# Port.net
KiCad netlist of a schematic drawn in Altium Designer
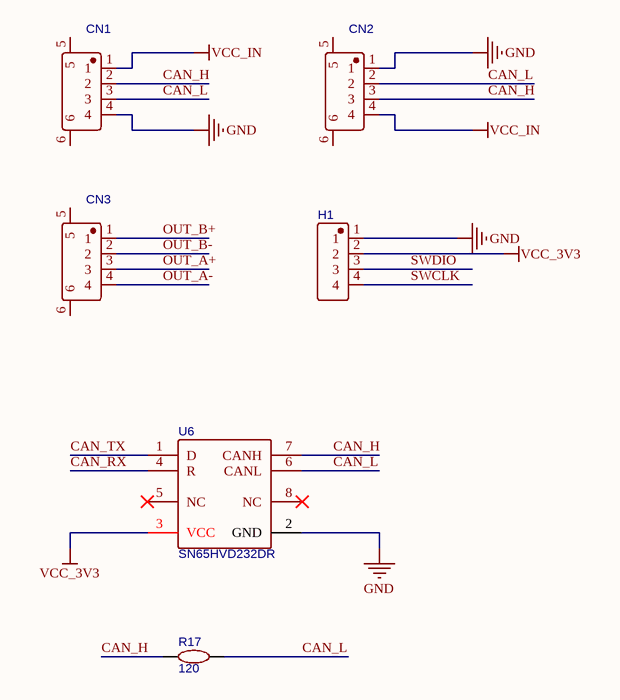
[diagram p0: Port.SchDoc]

(export (version "E")
  (design (tool "Eeschema 10.0.6"))
  (components
    (comp (ref "CN1")
      (value "~")
      (footprint "CONN-SMD_4P-P2.50-WAFER-254W-4P")
      (fields
        (field (name "BOM_SUPPLIER PART") "C2856745")
        (field (name "BOM_MANUFACTURER PART") "WAFER-254W-4P")
        (field (name "CONTRIBUTOR") "LCSC")
      )
      (libsource (lib "4P 2.54 WTB") (part "WAFER-254W-4P"))
    )
    (comp (ref "CN2")
      (value "~")
      (footprint "CONN-SMD_4P-P2.50-WAFER-254W-4P")
      (fields
        (field (name "BOM_SUPPLIER PART") "C2856745")
        (field (name "BOM_MANUFACTURER PART") "WAFER-254W-4P")
        (field (name "CONTRIBUTOR") "LCSC")
      )
      (libsource (lib "4P 2.54 WTB") (part "WAFER-254W-4P"))
    )
    (comp (ref "CN3")
      (value "~")
      (footprint "CONN-SMD_4P-P2.50-WAFER-254W-4P")
      (fields
        (field (name "BOM_SUPPLIER PART") "C2856745")
        (field (name "BOM_MANUFACTURER PART") "WAFER-254W-4P")
        (field (name "CONTRIBUTOR") "LCSC")
      )
      (libsource (lib "4P 2.54 WTB") (part "WAFER-254W-4P"))
    )
    (comp (ref "H1")
      (value "~")
      (footprint "HDR-TH_4P-P2.54-H-M-W10.4")
      (fields
        (field (name "BOM_SUPPLIER PART") "C91552")
        (field (name "BOM_MANUFACTURER PART") "2.54-1*4P反弯排针")
        (field (name "CONTRIBUTOR") "LCSC")
      )
      (libsource (lib "4P 2.54 bend") (part "2.54-1*4P反弯排针"))
    )
    (comp (ref "R17")
      (value "120")
      (footprint "R0603")
      (fields
        (field (name "BOM_MANUFACTURER PART") "0603WAF1200T5E")
        (field (name "BOM_SUPPLIER PART") "C22787")
      )
      (libsource (lib "120R") (part "120"))
    )
    (comp (ref "U6")
      (value "SN65HVD232DR")
      (footprint "SOIC-8_L5.0-W4.0-P1.27-LS6.0-BL")
      (fields (field (name "BOM_SUPPLIER PART") "C30530"))
      (libsource (lib "SN65HVD232DR") (part "SN65HVD232DR"))
    )
  )
  (nets
    (net (code "1") (name "/CAN_H") (class "Default")
      (node (ref "CN1") (pin "2") (pinfunction "2_2") (pintype "passive"))
      (node (ref "CN2") (pin "3") (pinfunction "3_3") (pintype "passive"))
      (node (ref "R17") (pin "1") (pinfunction "1_1") (pintype "passive"))
      (node (ref "U6") (pin "7") (pinfunction "CANH_7") (pintype "passive"))
    )
    (net (code "2") (name "/CAN_L") (class "Default")
      (node (ref "CN1") (pin "3") (pinfunction "3_3") (pintype "passive"))
      (node (ref "CN2") (pin "2") (pinfunction "2_2") (pintype "passive"))
      (node (ref "R17") (pin "2") (pinfunction "2_2") (pintype "passive"))
      (node (ref "U6") (pin "6") (pinfunction "CANL_6") (pintype "passive"))
    )
    (net (code "3") (name "/CAN_RX") (class "Default")
      (node (ref "U6") (pin "4") (pinfunction "R_4") (pintype "passive"))
    )
    (net (code "4") (name "/CAN_TX") (class "Default")
      (node (ref "U6") (pin "1") (pinfunction "D_1") (pintype "passive"))
    )
    (net (code "5") (name "/OUT_A+") (class "Default")
      (node (ref "CN3") (pin "3") (pinfunction "3_3") (pintype "passive"))
    )
    (net (code "6") (name "/OUT_A-") (class "Default")
      (node (ref "CN3") (pin "4") (pinfunction "4_4") (pintype "passive"))
    )
    (net (code "7") (name "/OUT_B+") (class "Default")
      (node (ref "CN3") (pin "1") (pinfunction "1_1") (pintype "passive"))
    )
    (net (code "8") (name "/OUT_B-") (class "Default")
      (node (ref "CN3") (pin "2") (pinfunction "2_2") (pintype "passive"))
    )
    (net (code "9") (name "/SWCLK") (class "Default")
      (node (ref "H1") (pin "4") (pinfunction "4_4") (pintype "passive"))
    )
    (net (code "10") (name "/SWDIO") (class "Default")
      (node (ref "H1") (pin "3") (pinfunction "3_3") (pintype "passive"))
    )
    (net (code "11") (name "GND") (class "Default")
      (node (ref "CN1") (pin "4") (pinfunction "4_4") (pintype "passive"))
      (node (ref "CN2") (pin "1") (pinfunction "1_1") (pintype "passive"))
      (node (ref "H1") (pin "1") (pinfunction "1_1") (pintype "passive"))
      (node (ref "U6") (pin "2") (pinfunction "GND_2") (pintype "passive"))
    )
    (net (code "12") (name "VCC_3V3") (class "Default")
      (node (ref "H1") (pin "2") (pinfunction "2_2") (pintype "passive"))
      (node (ref "U6") (pin "3") (pinfunction "VCC_3") (pintype "passive"))
    )
    (net (code "13") (name "VCC_IN") (class "Default")
      (node (ref "CN1") (pin "1") (pinfunction "1_1") (pintype "passive"))
      (node (ref "CN2") (pin "4") (pinfunction "4_4") (pintype "passive"))
    )
    (net (code "14") (name "unconnected-(CN1-Pad5)") (class "Default")
      (node (ref "CN1") (pin "5") (pinfunction "5_5") (pintype "passive"))
    )
    (net (code "15") (name "unconnected-(CN1-Pad6)") (class "Default")
      (node (ref "CN1") (pin "6") (pinfunction "6_6") (pintype "passive"))
    )
    (net (code "16") (name "unconnected-(CN2-Pad5)") (class "Default")
      (node (ref "CN2") (pin "5") (pinfunction "5_5") (pintype "passive"))
    )
    (net (code "17") (name "unconnected-(CN2-Pad6)") (class "Default")
      (node (ref "CN2") (pin "6") (pinfunction "6_6") (pintype "passive"))
    )
    (net (code "18") (name "unconnected-(CN3-Pad5)") (class "Default")
      (node (ref "CN3") (pin "5") (pinfunction "5_5") (pintype "passive"))
    )
    (net (code "19") (name "unconnected-(CN3-Pad6)") (class "Default")
      (node (ref "CN3") (pin "6") (pinfunction "6_6") (pintype "passive"))
    )
    (net (code "20") (name "unconnected-(U6-NC-Pad5)") (class "Default")
      (node (ref "U6") (pin "5") (pinfunction "NC_5") (pintype "passive+no_connect"))
    )
    (net (code "21") (name "unconnected-(U6-NC-Pad8)") (class "Default")
      (node (ref "U6") (pin "8") (pinfunction "NC_8") (pintype "passive+no_connect"))
    )
  )
)
